# MaxMotornRF52840.net
KiCad netlist of a schematic drawn in EAGLE
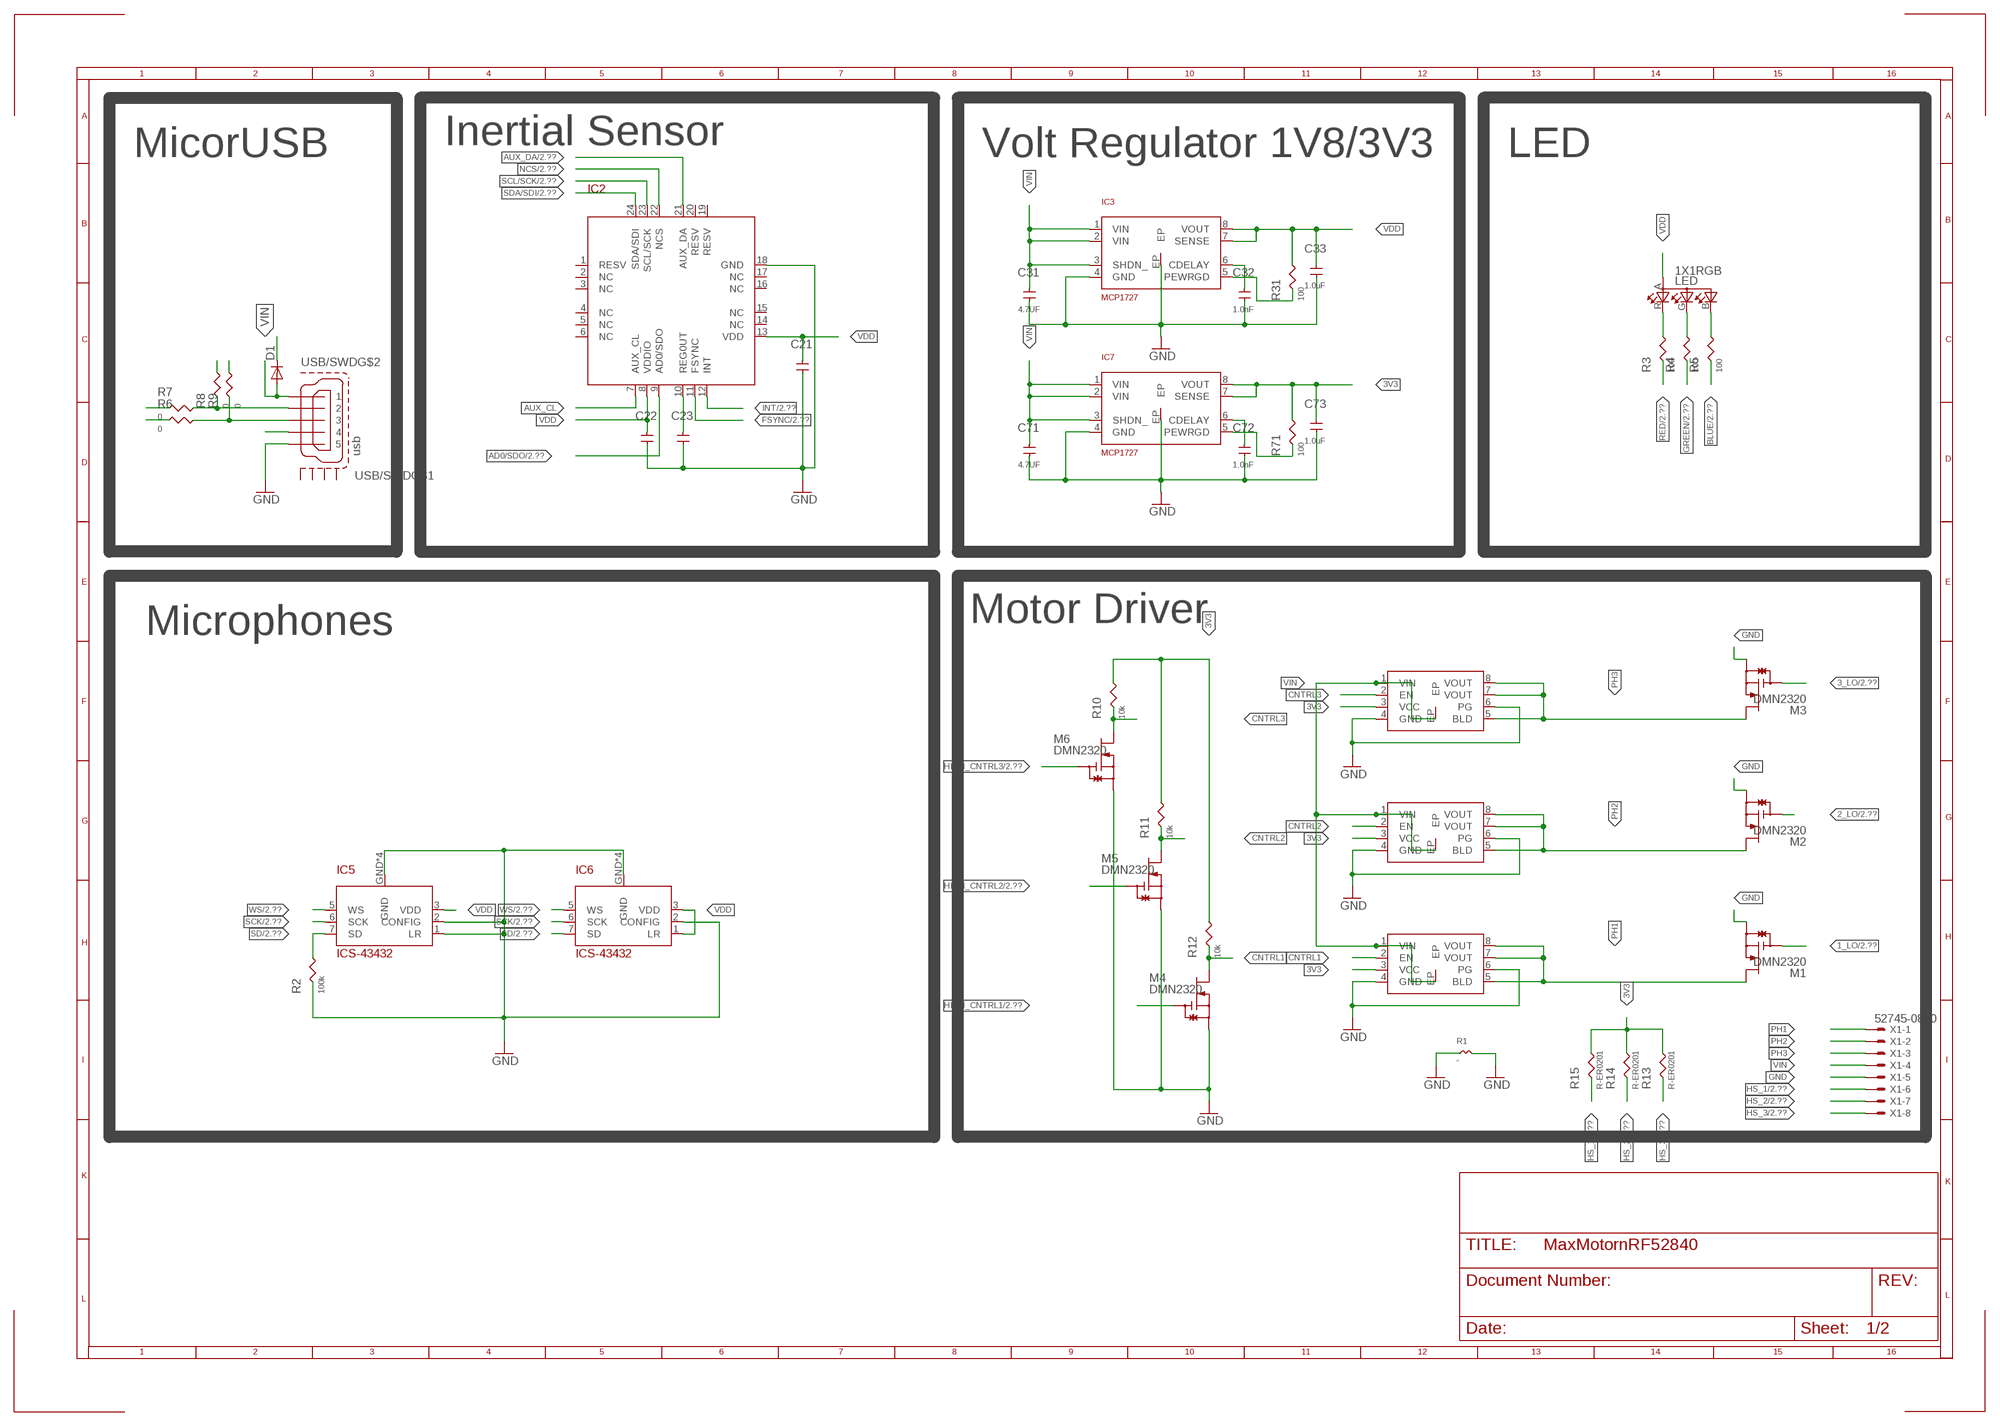
[diagram p0: schematic, sheet 1]
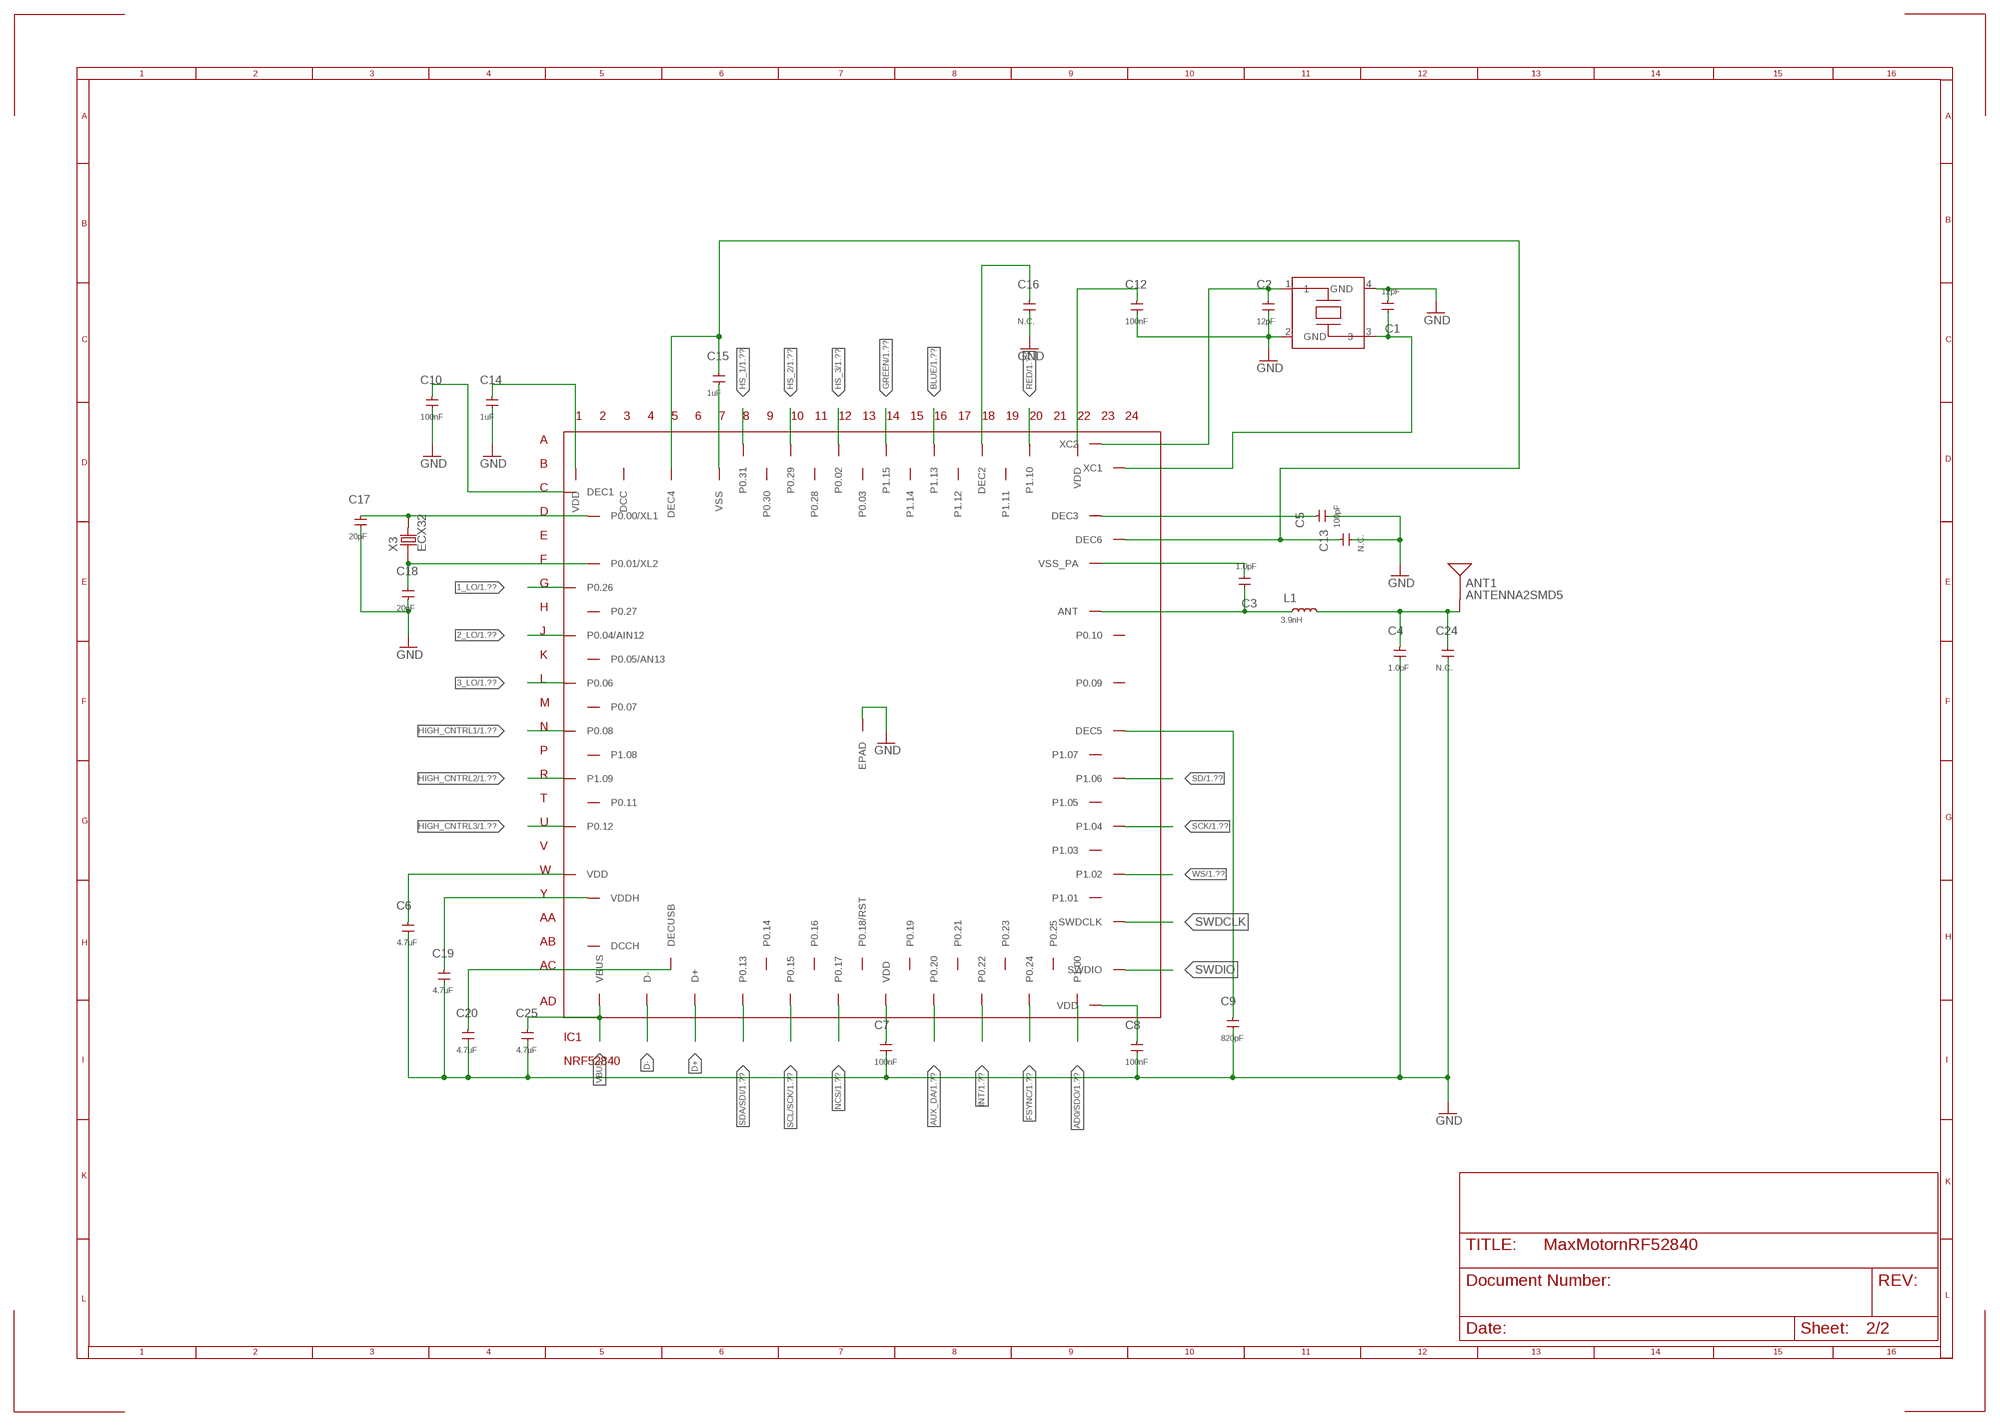
[diagram p1: schematic, sheet 2]

(export (version "E")
  (design (tool "Eeschema 10.0.6"))
  (components
    (comp (ref "ANT1")
      (value "ANTENNA2SMD5")
      (footprint "eagle-import:ANTENNA-CHIP5")
      (libsource (lib "eagle-import") (part "ANTENNA2SMD5"))
    )
    (comp (ref "C1")
      (value "12pF")
      (footprint "eagle-import:C0201")
      (libsource (lib "eagle-import") (part "C-ER201"))
    )
    (comp (ref "C2")
      (value "12pF")
      (footprint "eagle-import:C0201")
      (libsource (lib "eagle-import") (part "C-ER201"))
    )
    (comp (ref "C3")
      (value "1.0pF")
      (footprint "eagle-import:C0201")
      (libsource (lib "eagle-import") (part "C-ER201"))
    )
    (comp (ref "C4")
      (value "1.0pF")
      (footprint "eagle-import:C0201")
      (libsource (lib "eagle-import") (part "C-ER201"))
    )
    (comp (ref "C5")
      (value "100pF")
      (footprint "eagle-import:C0201")
      (libsource (lib "eagle-import") (part "C-ER201"))
    )
    (comp (ref "C6")
      (value "4.7uF")
      (footprint "eagle-import:C0402")
      (libsource (lib "eagle-import") (part "C-ERC0402"))
    )
    (comp (ref "C7")
      (value "100nF")
      (footprint "eagle-import:C0201")
      (libsource (lib "eagle-import") (part "C-ER201"))
    )
    (comp (ref "C8")
      (value "100nF")
      (footprint "eagle-import:C0201")
      (libsource (lib "eagle-import") (part "C-ER201"))
    )
    (comp (ref "C9")
      (value "820pF")
      (footprint "eagle-import:C0201")
      (libsource (lib "eagle-import") (part "C-ER201"))
    )
    (comp (ref "C10")
      (value "100nF")
      (footprint "eagle-import:C0201")
      (libsource (lib "eagle-import") (part "C-ER201"))
    )
    (comp (ref "C12")
      (value "100nF")
      (footprint "eagle-import:C0201")
      (libsource (lib "eagle-import") (part "C-ER201"))
    )
    (comp (ref "C13")
      (value "N.C.")
      (footprint "eagle-import:C0201")
      (libsource (lib "eagle-import") (part "C-ER201"))
    )
    (comp (ref "C14")
      (value "1uF")
      (footprint "eagle-import:C0201")
      (libsource (lib "eagle-import") (part "C-ER201"))
    )
    (comp (ref "C15")
      (value "1uF")
      (footprint "eagle-import:C0201")
      (libsource (lib "eagle-import") (part "C-ER201"))
    )
    (comp (ref "C16")
      (value "N.C.")
      (footprint "eagle-import:C0201")
      (libsource (lib "eagle-import") (part "C-ER201"))
    )
    (comp (ref "C17")
      (value "20pF")
      (footprint "eagle-import:C0201")
      (libsource (lib "eagle-import") (part "C-ER201"))
    )
    (comp (ref "C18")
      (value "20pF")
      (footprint "eagle-import:C0201")
      (libsource (lib "eagle-import") (part "C-ER201"))
    )
    (comp (ref "C19")
      (value "4.7uF")
      (footprint "eagle-import:C0402")
      (libsource (lib "eagle-import") (part "C-ERC0402"))
    )
    (comp (ref "C20")
      (value "4.7uF")
      (footprint "eagle-import:C0402")
      (libsource (lib "eagle-import") (part "C-ERC0402"))
    )
    (comp (ref "C24")
      (value "N.C.")
      (footprint "eagle-import:C0201")
      (libsource (lib "eagle-import") (part "C-ER201"))
    )
    (comp (ref "C25")
      (value "4.7uF")
      (footprint "eagle-import:C0402")
      (libsource (lib "eagle-import") (part "C-ERC0402"))
    )
    (comp (ref "IC1")
      (value "NRF52840")
      (footprint "eagle-import:AQFN73")
      (libsource (lib "eagle-import") (part "NRF52840"))
    )
    (comp (ref "L1")
      (value "3.9nH")
      (footprint "eagle-import:C0201@1")
      (libsource (lib "eagle-import") (part "L-ER0201"))
    )
    (comp (ref "X2")
      (value "ABM12")
      (footprint "eagle-import:ABM12")
      (libsource (lib "eagle-import") (part "ABM12"))
    )
    (comp (ref "X3")
      (value "ECX32")
      (footprint "eagle-import:ECX39")
      (libsource (lib "eagle-import") (part "ECX32"))
    )
    (comp (ref "C21")
      (value "C-ER201")
      (footprint "eagle-import:C0201")
      (libsource (lib "eagle-import") (part "C-ER201"))
    )
    (comp (ref "C22")
      (value "C-ER201")
      (footprint "eagle-import:C0201")
      (libsource (lib "eagle-import") (part "C-ER201"))
    )
    (comp (ref "C23")
      (value "C-ER201")
      (footprint "eagle-import:C0201")
      (libsource (lib "eagle-import") (part "C-ER201"))
    )
    (comp (ref "C31")
      (value "4.7UF")
      (footprint "eagle-import:C0402")
      (libsource (lib "eagle-import") (part "C-ERC0402"))
    )
    (comp (ref "C32")
      (value "1.0nF")
      (footprint "eagle-import:C0201")
      (libsource (lib "eagle-import") (part "C-ER201"))
    )
    (comp (ref "C33")
      (value "1.0uF")
      (footprint "eagle-import:C0201")
      (libsource (lib "eagle-import") (part "C-ER201"))
    )
    (comp (ref "C71")
      (value "4.7UF")
      (footprint "eagle-import:C0402")
      (libsource (lib "eagle-import") (part "C-ERC0402"))
    )
    (comp (ref "C72")
      (value "1.0nF")
      (footprint "eagle-import:C0201")
      (libsource (lib "eagle-import") (part "C-ER201"))
    )
    (comp (ref "C73")
      (value "1.0uF")
      (footprint "eagle-import:C0201")
      (libsource (lib "eagle-import") (part "C-ER201"))
    )
    (comp (ref "D1")
      (value "DIODE-SOD123")
      (footprint "eagle-import:SOD123")
      (libsource (lib "eagle-import") (part "DIODE-SOD123"))
    )
    (comp (ref "IC2")
      (value "ICM20948")
      (footprint "eagle-import:3X3_24_QFN_CORRECTED")
      (libsource (lib "eagle-import") (part "ICM20948"))
    )
    (comp (ref "IC3")
      (value "MCP1727")
      (footprint "eagle-import:DFN8-3X3")
      (libsource (lib "eagle-import") (part "MCP1727"))
    )
    (comp (ref "IC5")
      (value "ICS-43432")
      (footprint "eagle-import:ICS-43432")
      (libsource (lib "eagle-import") (part "ICS-43432"))
    )
    (comp (ref "IC6")
      (value "ICS-43432")
      (footprint "eagle-import:ICS-43432")
      (libsource (lib "eagle-import") (part "ICS-43432"))
    )
    (comp (ref "IC7")
      (value "MCP1727")
      (footprint "eagle-import:DFN8-3X3")
      (libsource (lib "eagle-import") (part "MCP1727"))
    )
    (comp (ref "LED")
      (value "1X1RGB")
      (footprint "eagle-import:1X1")
      (libsource (lib "eagle-import") (part "1X1RGB"))
    )
    (comp (ref "M1")
      (value "DMN2320")
      (footprint "eagle-import:AP02002")
      (libsource (lib "eagle-import") (part "DMN2320"))
    )
    (comp (ref "M2")
      (value "DMN2320")
      (footprint "eagle-import:AP02002")
      (libsource (lib "eagle-import") (part "DMN2320"))
    )
    (comp (ref "M3")
      (value "DMN2320")
      (footprint "eagle-import:AP02002")
      (libsource (lib "eagle-import") (part "DMN2320"))
    )
    (comp (ref "M4")
      (value "DMN2320")
      (footprint "eagle-import:AP02002")
      (libsource (lib "eagle-import") (part "DMN2320"))
    )
    (comp (ref "M5")
      (value "DMN2320")
      (footprint "eagle-import:AP02002")
      (libsource (lib "eagle-import") (part "DMN2320"))
    )
    (comp (ref "M6")
      (value "DMN2320")
      (footprint "eagle-import:AP02002")
      (libsource (lib "eagle-import") (part "DMN2320"))
    )
    (comp (ref "M7")
      (value "NCP45524/25")
      (footprint "eagle-import:DFN8")
      (libsource (lib "eagle-import") (part "NCP45524/25"))
    )
    (comp (ref "M8")
      (value "NCP45524/25")
      (footprint "eagle-import:DFN8")
      (libsource (lib "eagle-import") (part "NCP45524/25"))
    )
    (comp (ref "M9")
      (value "NCP45524/25")
      (footprint "eagle-import:DFN8")
      (libsource (lib "eagle-import") (part "NCP45524/25"))
    )
    (comp (ref "R1")
      (value "0")
      (footprint "eagle-import:R0805")
      (libsource (lib "eagle-import") (part "R-ER-TINY"))
    )
    (comp (ref "R2")
      (value "100k")
      (footprint "eagle-import:R0201")
      (libsource (lib "eagle-import") (part "R-ER0201"))
    )
    (comp (ref "R3")
      (value "100")
      (footprint "eagle-import:R0201")
      (libsource (lib "eagle-import") (part "R-ER0201"))
    )
    (comp (ref "R4")
      (value "100")
      (footprint "eagle-import:R0201")
      (libsource (lib "eagle-import") (part "R-ER0201"))
    )
    (comp (ref "R5")
      (value "100")
      (footprint "eagle-import:R0201")
      (libsource (lib "eagle-import") (part "R-ER0201"))
    )
    (comp (ref "R6")
      (value "0")
      (footprint "eagle-import:R0201")
      (libsource (lib "eagle-import") (part "R-ER0201"))
    )
    (comp (ref "R7")
      (value "0")
      (footprint "eagle-import:R0201")
      (libsource (lib "eagle-import") (part "R-ER0201"))
    )
    (comp (ref "R8")
      (value "0")
      (footprint "eagle-import:R0201")
      (libsource (lib "eagle-import") (part "R-ER0201"))
    )
    (comp (ref "R9")
      (value "0")
      (footprint "eagle-import:R0201")
      (libsource (lib "eagle-import") (part "R-ER0201"))
    )
    (comp (ref "R10")
      (value "10k")
      (footprint "eagle-import:R0201")
      (libsource (lib "eagle-import") (part "R-ER0201"))
    )
    (comp (ref "R11")
      (value "10k")
      (footprint "eagle-import:R0201")
      (libsource (lib "eagle-import") (part "R-ER0201"))
    )
    (comp (ref "R12")
      (value "10k")
      (footprint "eagle-import:R0201")
      (libsource (lib "eagle-import") (part "R-ER0201"))
    )
    (comp (ref "R13")
      (value "R-ER0201")
      (footprint "eagle-import:R0201")
      (libsource (lib "eagle-import") (part "R-ER0201"))
    )
    (comp (ref "R14")
      (value "R-ER0201")
      (footprint "eagle-import:R0201")
      (libsource (lib "eagle-import") (part "R-ER0201"))
    )
    (comp (ref "R15")
      (value "R-ER0201")
      (footprint "eagle-import:R0201")
      (libsource (lib "eagle-import") (part "R-ER0201"))
    )
    (comp (ref "R31")
      (value "100")
      (footprint "eagle-import:R0201")
      (libsource (lib "eagle-import") (part "R-ER0201"))
    )
    (comp (ref "R71")
      (value "100")
      (footprint "eagle-import:R0201")
      (libsource (lib "eagle-import") (part "R-ER0201"))
    )
    (comp (ref "USB/SWD")
      (value "usb")
      (footprint "eagle-import:ZX62R-B-5P")
      (libsource (lib "eagle-import") (part "MICRO-USB-SHIELD-ZX62R-B-5P"))
    )
    (comp (ref "X1")
      (value "52745-0890")
      (footprint "eagle-import:52745-0890")
      (libsource (lib "eagle-import") (part "52745-0890"))
    )
  )
  (nets
    (net (code "1") (name "1_LO") (class "Default")
      (node (ref "IC1") (pin "G1") (pinfunction "P0.26_G1") (pintype "bidirectional"))
      (node (ref "M1") (pin "G") (pinfunction "G_G") (pintype "passive"))
    )
    (net (code "2") (name "2_LO") (class "Default")
      (node (ref "IC1") (pin "J1") (pinfunction "P0.04/AIN12_J1") (pintype "bidirectional"))
      (node (ref "M2") (pin "G") (pinfunction "G_G") (pintype "passive"))
    )
    (net (code "3") (name "3V3") (class "Default")
      (node (ref "C73") (pin "2") (pinfunction "P$2_2") (pintype "bidirectional"))
      (node (ref "IC7") (pin "7") (pinfunction "SENSE_7") (pintype "bidirectional"))
      (node (ref "IC7") (pin "8") (pinfunction "VOUT_8") (pintype "bidirectional"))
      (node (ref "M7") (pin "3") (pinfunction "VCC_3") (pintype "bidirectional"))
      (node (ref "M8") (pin "3") (pinfunction "VCC_3") (pintype "bidirectional"))
      (node (ref "M9") (pin "3") (pinfunction "VCC_3") (pintype "bidirectional"))
      (node (ref "R10") (pin "2") (pinfunction "P$2_2") (pintype "bidirectional"))
      (node (ref "R11") (pin "2") (pinfunction "P$2_2") (pintype "bidirectional"))
      (node (ref "R12") (pin "2") (pinfunction "P$2_2") (pintype "bidirectional"))
      (node (ref "R13") (pin "2") (pinfunction "P$2_2") (pintype "bidirectional"))
      (node (ref "R14") (pin "2") (pinfunction "P$2_2") (pintype "bidirectional"))
      (node (ref "R15") (pin "2") (pinfunction "P$2_2") (pintype "bidirectional"))
      (node (ref "R71") (pin "2") (pinfunction "P$2_2") (pintype "bidirectional"))
    )
    (net (code "4") (name "3_LO") (class "Default")
      (node (ref "IC1") (pin "L1") (pinfunction "P0.06_L1") (pintype "bidirectional"))
      (node (ref "M3") (pin "G") (pinfunction "G_G") (pintype "passive"))
    )
    (net (code "5") (name "AD0{slash}SDO") (class "Default")
      (node (ref "IC1") (pin "AD22") (pinfunction "P1.00_AD22") (pintype "bidirectional"))
      (node (ref "IC2") (pin "9") (pinfunction "AD0/SDO_9") (pintype "bidirectional"))
    )
    (net (code "6") (name "AUX_CL") (class "Default")
      (node (ref "IC2") (pin "7") (pinfunction "AUX_CL_7") (pintype "bidirectional"))
    )
    (net (code "7") (name "AUX_DA") (class "Default")
      (node (ref "IC1") (pin "AD16") (pinfunction "P0.20_AD16") (pintype "bidirectional"))
      (node (ref "IC2") (pin "21") (pinfunction "AUX_DA_21") (pintype "bidirectional"))
    )
    (net (code "8") (name "BLUE") (class "Default")
      (node (ref "IC1") (pin "A16") (pinfunction "P1.13_A16") (pintype "bidirectional"))
      (node (ref "R5") (pin "1") (pinfunction "P$1_1") (pintype "bidirectional"))
    )
    (net (code "9") (name "CNTRL1") (class "Default")
      (node (ref "M4") (pin "D") (pinfunction "D_D") (pintype "passive"))
      (node (ref "M7") (pin "2") (pinfunction "EN_2") (pintype "bidirectional"))
      (node (ref "R12") (pin "1") (pinfunction "P$1_1") (pintype "bidirectional"))
    )
    (net (code "10") (name "CNTRL2") (class "Default")
      (node (ref "M5") (pin "D") (pinfunction "D_D") (pintype "passive"))
      (node (ref "M8") (pin "2") (pinfunction "EN_2") (pintype "bidirectional"))
      (node (ref "R11") (pin "1") (pinfunction "P$1_1") (pintype "bidirectional"))
    )
    (net (code "11") (name "CNTRL3") (class "Default")
      (node (ref "M6") (pin "D") (pinfunction "D_D") (pintype "passive"))
      (node (ref "M9") (pin "2") (pinfunction "EN_2") (pintype "bidirectional"))
      (node (ref "R10") (pin "1") (pinfunction "P$1_1") (pintype "bidirectional"))
    )
    (net (code "12") (name "D+") (class "Default")
      (node (ref "IC1") (pin "AD6") (pinfunction "D+_AD6") (pintype "bidirectional"))
      (node (ref "R6") (pin "1") (pinfunction "P$1_1") (pintype "bidirectional"))
    )
    (net (code "13") (name "D-") (class "Default")
      (node (ref "IC1") (pin "AD4") (pinfunction "D-_AD4") (pintype "bidirectional"))
      (node (ref "R7") (pin "1") (pinfunction "P$1_1") (pintype "bidirectional"))
    )
    (net (code "14") (name "FSYNC") (class "Default")
      (node (ref "IC1") (pin "AD20") (pinfunction "P0.24_AD20") (pintype "bidirectional"))
      (node (ref "IC2") (pin "11") (pinfunction "FSYNC_11") (pintype "bidirectional"))
    )
    (net (code "15") (name "GND") (class "Default")
      (node (ref "C1") (pin "1") (pinfunction "P$1_1") (pintype "bidirectional"))
      (node (ref "C10") (pin "1") (pinfunction "P$1_1") (pintype "bidirectional"))
      (node (ref "C12") (pin "1") (pinfunction "P$1_1") (pintype "bidirectional"))
      (node (ref "C13") (pin "1") (pinfunction "P$1_1") (pintype "bidirectional"))
      (node (ref "C14") (pin "1") (pinfunction "P$1_1") (pintype "bidirectional"))
      (node (ref "C15") (pin "1") (pinfunction "P$1_1") (pintype "bidirectional"))
      (node (ref "C16") (pin "1") (pinfunction "P$1_1") (pintype "bidirectional"))
      (node (ref "C17") (pin "1") (pinfunction "P$1_1") (pintype "bidirectional"))
      (node (ref "C18") (pin "1") (pinfunction "P$1_1") (pintype "bidirectional"))
      (node (ref "C19") (pin "1") (pinfunction "P$1_1") (pintype "bidirectional"))
      (node (ref "C2") (pin "1") (pinfunction "P$1_1") (pintype "bidirectional"))
      (node (ref "C20") (pin "1") (pinfunction "P$1_1") (pintype "bidirectional"))
      (node (ref "C21") (pin "1") (pinfunction "P$1_1") (pintype "bidirectional"))
      (node (ref "C22") (pin "1") (pinfunction "P$1_1") (pintype "bidirectional"))
      (node (ref "C23") (pin "1") (pinfunction "P$1_1") (pintype "bidirectional"))
      (node (ref "C24") (pin "1") (pinfunction "P$1_1") (pintype "bidirectional"))
      (node (ref "C25") (pin "1") (pinfunction "P$1_1") (pintype "bidirectional"))
      (node (ref "C3") (pin "1") (pinfunction "P$1_1") (pintype "bidirectional"))
      (node (ref "C31") (pin "1") (pinfunction "P$1_1") (pintype "bidirectional"))
      (node (ref "C32") (pin "1") (pinfunction "P$1_1") (pintype "bidirectional"))
      (node (ref "C33") (pin "1") (pinfunction "P$1_1") (pintype "bidirectional"))
      (node (ref "C4") (pin "1") (pinfunction "P$1_1") (pintype "bidirectional"))
      (node (ref "C5") (pin "1") (pinfunction "P$1_1") (pintype "bidirectional"))
      (node (ref "C6") (pin "1") (pinfunction "P$1_1") (pintype "bidirectional"))
      (node (ref "C7") (pin "1") (pinfunction "P$1_1") (pintype "bidirectional"))
      (node (ref "C71") (pin "1") (pinfunction "P$1_1") (pintype "bidirectional"))
      (node (ref "C72") (pin "1") (pinfunction "P$1_1") (pintype "bidirectional"))
      (node (ref "C73") (pin "1") (pinfunction "P$1_1") (pintype "bidirectional"))
      (node (ref "C8") (pin "1") (pinfunction "P$1_1") (pintype "bidirectional"))
      (node (ref "C9") (pin "1") (pinfunction "P$1_1") (pintype "bidirectional"))
      (node (ref "IC1") (pin "B7") (pinfunction "VSS_B7") (pintype "bidirectional"))
      (node (ref "IC1") (pin "EPAD") (pinfunction "EPAD_EPAD") (pintype "bidirectional"))
      (node (ref "IC1") (pin "F23") (pinfunction "VSS_PA_F23") (pintype "bidirectional"))
      (node (ref "IC2") (pin "18") (pinfunction "GND_18") (pintype "bidirectional"))
      (node (ref "IC3") (pin "4") (pinfunction "GND_4") (pintype "bidirectional"))
      (node (ref "IC3") (pin "EP") (pinfunction "EP_EP") (pintype "bidirectional"))
      (node (ref "IC5") (pin "1") (pinfunction "LR_1") (pintype "bidirectional"))
      (node (ref "IC5") (pin "2") (pinfunction "CONFIG_2") (pintype "bidirectional"))
      (node (ref "IC5") (pin "GND") (pinfunction "GND_GND") (pintype "bidirectional"))
      (node (ref "IC5") (pin "GND@") (pinfunction "GND_GND@") (pintype "bidirectional"))
      (node (ref "IC5") (pin "GND@1") (pinfunction "GND_GND@1") (pintype "bidirectional"))
      (node (ref "IC5") (pin "GND@2") (pinfunction "GND_GND@2") (pintype "bidirectional"))
      (node (ref "IC6") (pin "2") (pinfunction "CONFIG_2") (pintype "bidirectional"))
      (node (ref "IC6") (pin "GND") (pinfunction "GND_GND") (pintype "bidirectional"))
      (node (ref "IC6") (pin "GND@") (pinfunction "GND_GND@") (pintype "bidirectional"))
      (node (ref "IC6") (pin "GND@1") (pinfunction "GND_GND@1") (pintype "bidirectional"))
      (node (ref "IC6") (pin "GND@2") (pinfunction "GND_GND@2") (pintype "bidirectional"))
      (node (ref "IC7") (pin "4") (pinfunction "GND_4") (pintype "bidirectional"))
      (node (ref "IC7") (pin "EP") (pinfunction "EP_EP") (pintype "bidirectional"))
      (node (ref "M1") (pin "S") (pinfunction "S_S") (pintype "passive"))
      (node (ref "M2") (pin "S") (pinfunction "S_S") (pintype "passive"))
      (node (ref "M3") (pin "S") (pinfunction "S_S") (pintype "passive"))
      (node (ref "M4") (pin "S") (pinfunction "S_S") (pintype "passive"))
      (node (ref "M5") (pin "S") (pinfunction "S_S") (pintype "passive"))
      (node (ref "M6") (pin "S") (pinfunction "S_S") (pintype "passive"))
      (node (ref "M7") (pin "4") (pinfunction "GND_4") (pintype "bidirectional"))
      (node (ref "M7") (pin "6") (pinfunction "PG_6") (pintype "bidirectional"))
      (node (ref "M8") (pin "4") (pinfunction "GND_4") (pintype "bidirectional"))
      (node (ref "M8") (pin "6") (pinfunction "PG_6") (pintype "bidirectional"))
      (node (ref "M9") (pin "4") (pinfunction "GND_4") (pintype "bidirectional"))
      (node (ref "M9") (pin "6") (pinfunction "PG_6") (pintype "bidirectional"))
      (node (ref "R1") (pin "1") (pinfunction "P$1_1") (pintype "bidirectional"))
      (node (ref "R1") (pin "2") (pinfunction "P$2_2") (pintype "bidirectional"))
      (node (ref "R2") (pin "1") (pinfunction "P$1_1") (pintype "bidirectional"))
      (node (ref "USB/SWD") (pin "1") (pinfunction "5_1") (pintype "input"))
      (node (ref "X1") (pin "5") (pinfunction "S_5") (pintype "passive"))
      (node (ref "X2") (pin "2") (pinfunction "GND_2") (pintype "bidirectional"))
      (node (ref "X2") (pin "4") (pinfunction "GND_4") (pintype "bidirectional"))
    )
    (net (code "16") (name "GREEN") (class "Default")
      (node (ref "IC1") (pin "A14") (pinfunction "P1.15_A14") (pintype "bidirectional"))
      (node (ref "R4") (pin "1") (pinfunction "P$1_1") (pintype "bidirectional"))
    )
    (net (code "17") (name "HIGH_CNTRL1") (class "Default")
      (node (ref "IC1") (pin "N1") (pinfunction "P0.08_N1") (pintype "bidirectional"))
      (node (ref "M4") (pin "G") (pinfunction "G_G") (pintype "passive"))
    )
    (net (code "18") (name "HIGH_CNTRL2") (class "Default")
      (node (ref "IC1") (pin "R1") (pinfunction "P1.09_R1") (pintype "bidirectional"))
      (node (ref "M5") (pin "G") (pinfunction "G_G") (pintype "passive"))
    )
    (net (code "19") (name "HIGH_CNTRL3") (class "Default")
      (node (ref "IC1") (pin "U1") (pinfunction "P0.12_U1") (pintype "bidirectional"))
      (node (ref "M6") (pin "G") (pinfunction "G_G") (pintype "passive"))
    )
    (net (code "20") (name "HS_1") (class "Default")
      (node (ref "IC1") (pin "A8") (pinfunction "P0.31_A8") (pintype "bidirectional"))
      (node (ref "R15") (pin "1") (pinfunction "P$1_1") (pintype "bidirectional"))
      (node (ref "X1") (pin "6") (pinfunction "S_6") (pintype "passive"))
    )
    (net (code "21") (name "HS_2") (class "Default")
      (node (ref "IC1") (pin "A10") (pinfunction "P0.29_A10") (pintype "bidirectional"))
      (node (ref "R14") (pin "1") (pinfunction "P$1_1") (pintype "bidirectional"))
      (node (ref "X1") (pin "7") (pinfunction "S_7") (pintype "passive"))
    )
    (net (code "22") (name "HS_3") (class "Default")
      (node (ref "IC1") (pin "A12") (pinfunction "P0.02_A12") (pintype "bidirectional"))
      (node (ref "R13") (pin "1") (pinfunction "P$1_1") (pintype "bidirectional"))
      (node (ref "X1") (pin "8") (pinfunction "S_8") (pintype "passive"))
    )
    (net (code "23") (name "INT") (class "Default")
      (node (ref "IC1") (pin "AD18") (pinfunction "P0.22_AD18") (pintype "bidirectional"))
      (node (ref "IC2") (pin "12") (pinfunction "INT_12") (pintype "bidirectional"))
    )
    (net (code "24") (name "NCS") (class "Default")
      (node (ref "IC1") (pin "AD12") (pinfunction "P0.17_AD12") (pintype "bidirectional"))
      (node (ref "IC2") (pin "22") (pinfunction "NCS_22") (pintype "bidirectional"))
    )
    (net (code "25") (name "Net-(ANT1-SIGNAL)") (class "Default")
      (node (ref "ANT1") (pin "FEED") (pinfunction "SIGNAL_FEED") (pintype "bidirectional"))
      (node (ref "C24") (pin "2") (pinfunction "P$2_2") (pintype "bidirectional"))
      (node (ref "C4") (pin "2") (pinfunction "P$2_2") (pintype "bidirectional"))
      (node (ref "L1") (pin "2") (pinfunction "P$2_2") (pintype "bidirectional"))
    )
    (net (code "26") (name "Net-(C1-P$2)") (class "Default")
      (node (ref "C1") (pin "2") (pinfunction "P$2_2") (pintype "bidirectional"))
      (node (ref "IC1") (pin "B24") (pinfunction "XC1_B24") (pintype "bidirectional"))
      (node (ref "X2") (pin "3") (pinfunction "3_3") (pintype "bidirectional"))
    )
    (net (code "27") (name "Net-(C2-P$2)") (class "Default")
      (node (ref "C2") (pin "2") (pinfunction "P$2_2") (pintype "bidirectional"))
      (node (ref "IC1") (pin "A23") (pinfunction "XC2_A23") (pintype "bidirectional"))
      (node (ref "X2") (pin "1") (pinfunction "1_1") (pintype "bidirectional"))
    )
    (net (code "28") (name "Net-(C3-P$2)") (class "Default")
      (node (ref "C3") (pin "2") (pinfunction "P$2_2") (pintype "bidirectional"))
      (node (ref "IC1") (pin "H23") (pinfunction "ANT_H23") (pintype "bidirectional"))
      (node (ref "L1") (pin "1") (pinfunction "P$1_1") (pintype "bidirectional"))
    )
    (net (code "29") (name "Net-(C5-P$2)") (class "Default")
      (node (ref "C5") (pin "2") (pinfunction "P$2_2") (pintype "bidirectional"))
      (node (ref "IC1") (pin "D23") (pinfunction "DEC3_D23") (pintype "bidirectional"))
    )
    (net (code "30") (name "Net-(C9-P$2)") (class "Default")
      (node (ref "C9") (pin "2") (pinfunction "P$2_2") (pintype "bidirectional"))
      (node (ref "IC1") (pin "N24") (pinfunction "DEC5_N24") (pintype "bidirectional"))
    )
    (net (code "31") (name "Net-(C13-P$2)") (class "Default")
      (node (ref "C13") (pin "2") (pinfunction "P$2_2") (pintype "bidirectional"))
      (node (ref "C15") (pin "2") (pinfunction "P$2_2") (pintype "bidirectional"))
      (node (ref "IC1") (pin "B5") (pinfunction "DEC4_B5") (pintype "bidirectional"))
      (node (ref "IC1") (pin "E24") (pinfunction "DEC6_E24") (pintype "bidirectional"))
    )
    (net (code "32") (name "Net-(C14-P$2)") (class "Default")
      (node (ref "C14") (pin "2") (pinfunction "P$2_2") (pintype "bidirectional"))
      (node (ref "IC1") (pin "B1") (pinfunction "VDD_B1") (pintype "bidirectional"))
    )
    (net (code "33") (name "Net-(C16-P$2)") (class "Default")
      (node (ref "C16") (pin "2") (pinfunction "P$2_2") (pintype "bidirectional"))
      (node (ref "IC1") (pin "A18") (pinfunction "DEC2_A18") (pintype "bidirectional"))
    )
    (net (code "34") (name "Net-(C17-P$2)") (class "Default")
      (node (ref "C17") (pin "2") (pinfunction "P$2_2") (pintype "bidirectional"))
      (node (ref "IC1") (pin "D2") (pinfunction "P0.00/XL1_D2") (pintype "bidirectional"))
      (node (ref "X3") (pin "P$2") (pinfunction "2_P$2") (pintype "passive"))
    )
    (net (code "35") (name "Net-(C18-P$2)") (class "Default")
      (node (ref "C18") (pin "2") (pinfunction "P$2_2") (pintype "bidirectional"))
      (node (ref "IC1") (pin "F2") (pinfunction "P0.01/XL2_F2") (pintype "bidirectional"))
      (node (ref "X3") (pin "P$1") (pinfunction "1_P$1") (pintype "passive"))
    )
    (net (code "36") (name "Net-(C20-P$2)") (class "Default")
      (node (ref "C20") (pin "2") (pinfunction "P$2_2") (pintype "bidirectional"))
      (node (ref "IC1") (pin "AC5") (pinfunction "DECUSB_AC5") (pintype "bidirectional"))
    )
    (net (code "37") (name "Net-(C23-P$2)") (class "Default")
      (node (ref "C23") (pin "2") (pinfunction "P$2_2") (pintype "bidirectional"))
      (node (ref "IC2") (pin "10") (pinfunction "REG0UT_10") (pintype "bidirectional"))
    )
    (net (code "38") (name "Net-(C32-P$2)") (class "Default")
      (node (ref "C32") (pin "2") (pinfunction "P$2_2") (pintype "bidirectional"))
      (node (ref "IC3") (pin "6") (pinfunction "CDELAY_6") (pintype "bidirectional"))
    )
    (net (code "39") (name "Net-(C72-P$2)") (class "Default")
      (node (ref "C72") (pin "2") (pinfunction "P$2_2") (pintype "bidirectional"))
      (node (ref "IC7") (pin "6") (pinfunction "CDELAY_6") (pintype "bidirectional"))
    )
    (net (code "40") (name "Net-(IC3-PEWRGD)") (class "Default")
      (node (ref "IC3") (pin "5") (pinfunction "PEWRGD_5") (pintype "bidirectional"))
      (node (ref "R31") (pin "1") (pinfunction "P$1_1") (pintype "bidirectional"))
    )
    (net (code "41") (name "Net-(IC7-PEWRGD)") (class "Default")
      (node (ref "IC7") (pin "5") (pinfunction "PEWRGD_5") (pintype "bidirectional"))
      (node (ref "R71") (pin "1") (pinfunction "P$1_1") (pintype "bidirectional"))
    )
    (net (code "42") (name "Net-(LED-CBLUE)") (class "Default")
      (node (ref "LED") (pin "G") (pinfunction "CBLUE_G") (pintype "passive"))
      (node (ref "R4") (pin "2") (pinfunction "P$2_2") (pintype "bidirectional"))
    )
    (net (code "43") (name "Net-(LED-CGREEN)") (class "Default")
      (node (ref "LED") (pin "B") (pinfunction "CGREEN_B") (pintype "passive"))
      (node (ref "R5") (pin "2") (pinfunction "P$2_2") (pintype "bidirectional"))
    )
    (net (code "44") (name "Net-(LED-CRED)") (class "Default")
      (node (ref "LED") (pin "R") (pinfunction "CRED_R") (pintype "passive"))
      (node (ref "R3") (pin "2") (pinfunction "P$2_2") (pintype "bidirectional"))
    )
    (net (code "45") (name "Net-(R6-P$2)") (class "Default")
      (node (ref "R6") (pin "2") (pinfunction "P$2_2") (pintype "bidirectional"))
      (node (ref "R9") (pin "1") (pinfunction "P$1_1") (pintype "bidirectional"))
      (node (ref "USB/SWD") (pin "3") (pinfunction "3_3") (pintype "input"))
    )
    (net (code "46") (name "Net-(R7-P$2)") (class "Default")
      (node (ref "R7") (pin "2") (pinfunction "P$2_2") (pintype "bidirectional"))
      (node (ref "R8") (pin "1") (pinfunction "P$1_1") (pintype "bidirectional"))
      (node (ref "USB/SWD") (pin "4") (pinfunction "2_4") (pintype "input"))
    )
    (net (code "47") (name "PH1") (class "Default")
      (node (ref "M1") (pin "D") (pinfunction "D_D") (pintype "passive"))
      (node (ref "M7") (pin "5") (pinfunction "BLD_5") (pintype "bidirectional"))
      (node (ref "M7") (pin "7") (pinfunction "VOUT_7") (pintype "bidirectional"))
      (node (ref "M7") (pin "8") (pinfunction "VOUT_8") (pintype "bidirectional"))
      (node (ref "X1") (pin "1") (pinfunction "S_1") (pintype "passive"))
    )
    (net (code "48") (name "PH2") (class "Default")
      (node (ref "M2") (pin "D") (pinfunction "D_D") (pintype "passive"))
      (node (ref "M8") (pin "5") (pinfunction "BLD_5") (pintype "bidirectional"))
      (node (ref "M8") (pin "7") (pinfunction "VOUT_7") (pintype "bidirectional"))
      (node (ref "M8") (pin "8") (pinfunction "VOUT_8") (pintype "bidirectional"))
      (node (ref "X1") (pin "2") (pinfunction "S_2") (pintype "passive"))
    )
    (net (code "49") (name "PH3") (class "Default")
      (node (ref "M3") (pin "D") (pinfunction "D_D") (pintype "passive"))
      (node (ref "M9") (pin "5") (pinfunction "BLD_5") (pintype "bidirectional"))
      (node (ref "M9") (pin "7") (pinfunction "VOUT_7") (pintype "bidirectional"))
      (node (ref "M9") (pin "8") (pinfunction "VOUT_8") (pintype "bidirectional"))
      (node (ref "X1") (pin "3") (pinfunction "S_3") (pintype "passive"))
    )
    (net (code "50") (name "RED") (class "Default")
      (node (ref "IC1") (pin "A20") (pinfunction "P1.10_A20") (pintype "bidirectional"))
      (node (ref "R3") (pin "1") (pinfunction "P$1_1") (pintype "bidirectional"))
    )
    (net (code "51") (name "SCK") (class "Default")
      (node (ref "IC1") (pin "U24") (pinfunction "P1.04_U24") (pintype "bidirectional"))
      (node (ref "IC5") (pin "6") (pinfunction "SCK_6") (pintype "bidirectional"))
      (node (ref "IC6") (pin "6") (pinfunction "SCK_6") (pintype "bidirectional"))
    )
    (net (code "52") (name "SCL{slash}SCK") (class "Default")
      (node (ref "IC1") (pin "AD10") (pinfunction "P0.15_AD10") (pintype "bidirectional"))
      (node (ref "IC2") (pin "23") (pinfunction "SCL/SCK_23") (pintype "bidirectional"))
    )
    (net (code "53") (name "SD") (class "Default")
      (node (ref "IC1") (pin "R24") (pinfunction "P1.06_R24") (pintype "bidirectional"))
      (node (ref "IC5") (pin "7") (pinfunction "SD_7") (pintype "bidirectional"))
      (node (ref "IC6") (pin "7") (pinfunction "SD_7") (pintype "bidirectional"))
      (node (ref "R2") (pin "2") (pinfunction "P$2_2") (pintype "bidirectional"))
    )
    (net (code "54") (name "SDA{slash}SDI") (class "Default")
      (node (ref "IC1") (pin "AD8") (pinfunction "P0.13_AD8") (pintype "bidirectional"))
      (node (ref "IC2") (pin "24") (pinfunction "SDA/SDI_24") (pintype "bidirectional"))
    )
    (net (code "55") (name "SWDCLK") (class "Default")
      (node (ref "IC1") (pin "AA24") (pinfunction "SWDCLK_AA24") (pintype "bidirectional"))
      (node (ref "R9") (pin "2") (pinfunction "P$2_2") (pintype "bidirectional"))
    )
    (net (code "56") (name "SWDIO") (class "Default")
      (node (ref "IC1") (pin "AC24") (pinfunction "SWDIO_AC24") (pintype "bidirectional"))
      (node (ref "R8") (pin "2") (pinfunction "P$2_2") (pintype "bidirectional"))
    )
    (net (code "57") (name "VBUS") (class "Default")
      (node (ref "C19") (pin "2") (pinfunction "P$2_2") (pintype "bidirectional"))
      (node (ref "C25") (pin "2") (pinfunction "P$2_2") (pintype "bidirectional"))
      (node (ref "D1") (pin "C") (pinfunction "C_C") (pintype "passive"))
      (node (ref "IC1") (pin "AD2") (pinfunction "VBUS_AD2") (pintype "bidirectional"))
      (node (ref "IC1") (pin "Y2") (pinfunction "VDDH_Y2") (pintype "bidirectional"))
    )
    (net (code "58") (name "VDD") (class "Default")
      (node (ref "C10") (pin "2") (pinfunction "P$2_2") (pintype "bidirectional"))
      (node (ref "C12") (pin "2") (pinfunction "P$2_2") (pintype "bidirectional"))
      (node (ref "C21") (pin "2") (pinfunction "P$2_2") (pintype "bidirectional"))
      (node (ref "C22") (pin "2") (pinfunction "P$2_2") (pintype "bidirectional"))
      (node (ref "C33") (pin "2") (pinfunction "P$2_2") (pintype "bidirectional"))
      (node (ref "C6") (pin "2") (pinfunction "P$2_2") (pintype "bidirectional"))
      (node (ref "C7") (pin "2") (pinfunction "P$2_2") (pintype "bidirectional"))
      (node (ref "C8") (pin "2") (pinfunction "P$2_2") (pintype "bidirectional"))
      (node (ref "IC1") (pin "A22") (pinfunction "VDD_A22") (pintype "bidirectional"))
      (node (ref "IC1") (pin "AD14") (pinfunction "VDD_AD14") (pintype "bidirectional"))
      (node (ref "IC1") (pin "AD23") (pinfunction "VDD_AD23") (pintype "bidirectional"))
      (node (ref "IC1") (pin "C1") (pinfunction "DEC1_C1") (pintype "bidirectional"))
      (node (ref "IC1") (pin "W1") (pinfunction "VDD_W1") (pintype "bidirectional"))
      (node (ref "IC2") (pin "13") (pinfunction "VDD_13") (pintype "bidirectional"))
      (node (ref "IC2") (pin "8") (pinfunction "VDDIO_8") (pintype "bidirectional"))
      (node (ref "IC3") (pin "7") (pinfunction "SENSE_7") (pintype "bidirectional"))
      (node (ref "IC3") (pin "8") (pinfunction "VOUT_8") (pintype "bidirectional"))
      (node (ref "IC5") (pin "3") (pinfunction "VDD_3") (pintype "bidirectional"))
      (node (ref "IC6") (pin "1") (pinfunction "LR_1") (pintype "bidirectional"))
      (node (ref "IC6") (pin "3") (pinfunction "VDD_3") (pintype "bidirectional"))
      (node (ref "LED") (pin "A") (pinfunction "A2_A") (pintype "passive"))
      (node (ref "R31") (pin "2") (pinfunction "P$2_2") (pintype "bidirectional"))
    )
    (net (code "59") (name "VIN") (class "Default")
      (node (ref "C31") (pin "2") (pinfunction "P$2_2") (pintype "bidirectional"))
      (node (ref "C71") (pin "2") (pinfunction "P$2_2") (pintype "bidirectional"))
      (node (ref "D1") (pin "A") (pinfunction "A_A") (pintype "passive"))
      (node (ref "IC3") (pin "1") (pinfunction "VIN_1") (pintype "bidirectional"))
      (node (ref "IC3") (pin "2") (pinfunction "VIN_2") (pintype "bidirectional"))
      (node (ref "IC3") (pin "3") (pinfunction "SHDN__3") (pintype "bidirectional"))
      (node (ref "IC7") (pin "1") (pinfunction "VIN_1") (pintype "bidirectional"))
      (node (ref "IC7") (pin "2") (pinfunction "VIN_2") (pintype "bidirectional"))
      (node (ref "IC7") (pin "3") (pinfunction "SHDN__3") (pintype "bidirectional"))
      (node (ref "M7") (pin "1") (pinfunction "VIN_1") (pintype "bidirectional"))
      (node (ref "M7") (pin "EP") (pinfunction "EP_EP") (pintype "bidirectional"))
      (node (ref "M8") (pin "1") (pinfunction "VIN_1") (pintype "bidirectional"))
      (node (ref "M8") (pin "EP") (pinfunction "EP_EP") (pintype "bidirectional"))
      (node (ref "M9") (pin "1") (pinfunction "VIN_1") (pintype "bidirectional"))
      (node (ref "M9") (pin "EP") (pinfunction "EP_EP") (pintype "bidirectional"))
      (node (ref "USB/SWD") (pin "5") (pinfunction "1_5") (pintype "input"))
      (node (ref "X1") (pin "4") (pinfunction "S_4") (pintype "passive"))
    )
    (net (code "60") (name "WS") (class "Default")
      (node (ref "IC1") (pin "W24") (pinfunction "P1.02_W24") (pintype "bidirectional"))
      (node (ref "IC5") (pin "5") (pinfunction "WS_5") (pintype "bidirectional"))
      (node (ref "IC6") (pin "5") (pinfunction "WS_5") (pintype "bidirectional"))
    )
    (net (code "61") (name "unconnected-(IC1-DCC-PadB3)") (class "Default")
      (node (ref "IC1") (pin "B3") (pinfunction "DCC_B3") (pintype "bidirectional"))
    )
    (net (code "62") (name "unconnected-(IC1-DCCH-PadAB2)") (class "Default")
      (node (ref "IC1") (pin "AB2") (pinfunction "DCCH_AB2") (pintype "bidirectional"))
    )
    (net (code "63") (name "unconnected-(IC1-P0.03-PadB13)") (class "Default")
      (node (ref "IC1") (pin "B13") (pinfunction "P0.03_B13") (pintype "bidirectional"))
    )
    (net (code "64") (name "unconnected-(IC1-P0.05{slash}AN13-PadK2)") (class "Default")
      (node (ref "IC1") (pin "K2") (pinfunction "P0.05/AN13_K2") (pintype "bidirectional"))
    )
    (net (code "65") (name "unconnected-(IC1-P0.07-PadM2)") (class "Default")
      (node (ref "IC1") (pin "M2") (pinfunction "P0.07_M2") (pintype "bidirectional"))
    )
    (net (code "66") (name "unconnected-(IC1-P0.09-PadL24)") (class "Default")
      (node (ref "IC1") (pin "L24") (pinfunction "P0.09_L24") (pintype "bidirectional"))
    )
    (net (code "67") (name "unconnected-(IC1-P0.10-PadJ24)") (class "Default")
      (node (ref "IC1") (pin "J24") (pinfunction "P0.10_J24") (pintype "bidirectional"))
    )
    (net (code "68") (name "unconnected-(IC1-P0.11-PadT2)") (class "Default")
      (node (ref "IC1") (pin "T2") (pinfunction "P0.11_T2") (pintype "bidirectional"))
    )
    (net (code "69") (name "unconnected-(IC1-P0.14-PadAC9)") (class "Default")
      (node (ref "IC1") (pin "AC9") (pinfunction "P0.14_AC9") (pintype "bidirectional"))
    )
    (net (code "70") (name "unconnected-(IC1-P0.16-PadAC11)") (class "Default")
      (node (ref "IC1") (pin "AC11") (pinfunction "P0.16_AC11") (pintype "bidirectional"))
    )
    (net (code "71") (name "unconnected-(IC1-P0.18{slash}RST-PadAC13)") (class "Default")
      (node (ref "IC1") (pin "AC13") (pinfunction "P0.18/RST_AC13") (pintype "bidirectional"))
    )
    (net (code "72") (name "unconnected-(IC1-P0.19-PadAC15)") (class "Default")
      (node (ref "IC1") (pin "AC15") (pinfunction "P0.19_AC15") (pintype "bidirectional"))
    )
    (net (code "73") (name "unconnected-(IC1-P0.21-PadAC17)") (class "Default")
      (node (ref "IC1") (pin "AC17") (pinfunction "P0.21_AC17") (pintype "bidirectional"))
    )
    (net (code "74") (name "unconnected-(IC1-P0.23-PadAC19)") (class "Default")
      (node (ref "IC1") (pin "AC19") (pinfunction "P0.23_AC19") (pintype "bidirectional"))
    )
    (net (code "75") (name "unconnected-(IC1-P0.25-PadAC21)") (class "Default")
      (node (ref "IC1") (pin "AC21") (pinfunction "P0.25_AC21") (pintype "bidirectional"))
    )
    (net (code "76") (name "unconnected-(IC1-P0.27-PadH2)") (class "Default")
      (node (ref "IC1") (pin "H2") (pinfunction "P0.27_H2") (pintype "bidirectional"))
    )
    (net (code "77") (name "unconnected-(IC1-P0.28-PadB11)") (class "Default")
      (node (ref "IC1") (pin "B11") (pinfunction "P0.28_B11") (pintype "bidirectional"))
    )
    (net (code "78") (name "unconnected-(IC1-P0.30-PadB9)") (class "Default")
      (node (ref "IC1") (pin "B9") (pinfunction "P0.30_B9") (pintype "bidirectional"))
    )
    (net (code "79") (name "unconnected-(IC1-P1.01-PadY23)") (class "Default")
      (node (ref "IC1") (pin "Y23") (pinfunction "P1.01_Y23") (pintype "bidirectional"))
    )
    (net (code "80") (name "unconnected-(IC1-P1.03-PadV23)") (class "Default")
      (node (ref "IC1") (pin "V23") (pinfunction "P1.03_V23") (pintype "bidirectional"))
    )
    (net (code "81") (name "unconnected-(IC1-P1.05-PadT23)") (class "Default")
      (node (ref "IC1") (pin "T23") (pinfunction "P1.05_T23") (pintype "bidirectional"))
    )
    (net (code "82") (name "unconnected-(IC1-P1.07-PadP23)") (class "Default")
      (node (ref "IC1") (pin "P23") (pinfunction "P1.07_P23") (pintype "bidirectional"))
    )
    (net (code "83") (name "unconnected-(IC1-P1.08-PadP2)") (class "Default")
      (node (ref "IC1") (pin "P2") (pinfunction "P1.08_P2") (pintype "bidirectional"))
    )
    (net (code "84") (name "unconnected-(IC1-P1.11-PadB19)") (class "Default")
      (node (ref "IC1") (pin "B19") (pinfunction "P1.11_B19") (pintype "bidirectional"))
    )
    (net (code "85") (name "unconnected-(IC1-P1.12-PadB17)") (class "Default")
      (node (ref "IC1") (pin "B17") (pinfunction "P1.12_B17") (pintype "bidirectional"))
    )
    (net (code "86") (name "unconnected-(IC1-P1.14-PadB15)") (class "Default")
      (node (ref "IC1") (pin "B15") (pinfunction "P1.14_B15") (pintype "bidirectional"))
    )
    (net (code "87") (name "unconnected-(IC2-NC-Pad2)") (class "Default")
      (node (ref "IC2") (pin "2") (pinfunction "NC_2") (pintype "bidirectional"))
    )
    (net (code "88") (name "unconnected-(IC2-NC-Pad3)") (class "Default")
      (node (ref "IC2") (pin "3") (pinfunction "NC_3") (pintype "bidirectional"))
    )
    (net (code "89") (name "unconnected-(IC2-NC-Pad4)") (class "Default")
      (node (ref "IC2") (pin "4") (pinfunction "NC_4") (pintype "bidirectional"))
    )
    (net (code "90") (name "unconnected-(IC2-NC-Pad5)") (class "Default")
      (node (ref "IC2") (pin "5") (pinfunction "NC_5") (pintype "bidirectional"))
    )
    (net (code "91") (name "unconnected-(IC2-NC-Pad6)") (class "Default")
      (node (ref "IC2") (pin "6") (pinfunction "NC_6") (pintype "bidirectional"))
    )
    (net (code "92") (name "unconnected-(IC2-NC-Pad14)") (class "Default")
      (node (ref "IC2") (pin "14") (pinfunction "NC_14") (pintype "bidirectional"))
    )
    (net (code "93") (name "unconnected-(IC2-NC-Pad15)") (class "Default")
      (node (ref "IC2") (pin "15") (pinfunction "NC_15") (pintype "bidirectional"))
    )
    (net (code "94") (name "unconnected-(IC2-NC-Pad16)") (class "Default")
      (node (ref "IC2") (pin "16") (pinfunction "NC_16") (pintype "bidirectional"))
    )
    (net (code "95") (name "unconnected-(IC2-NC-Pad17)") (class "Default")
      (node (ref "IC2") (pin "17") (pinfunction "NC_17") (pintype "bidirectional"))
    )
    (net (code "96") (name "unconnected-(IC2-RESV-Pad1)") (class "Default")
      (node (ref "IC2") (pin "1") (pinfunction "RESV_1") (pintype "bidirectional"))
    )
    (net (code "97") (name "unconnected-(IC2-RESV-Pad19)") (class "Default")
      (node (ref "IC2") (pin "19") (pinfunction "RESV_19") (pintype "bidirectional"))
    )
    (net (code "98") (name "unconnected-(IC2-RESV-Pad20)") (class "Default")
      (node (ref "IC2") (pin "20") (pinfunction "RESV_20") (pintype "bidirectional"))
    )
    (net (code "99") (name "unconnected-(USB/SWDA-S1-PadM1)") (class "Default")
      (node (ref "USB/SWD") (pin "M1") (pinfunction "S1_M1") (pintype "passive"))
    )
    (net (code "100") (name "unconnected-(USB/SWDA-S2-PadM2)") (class "Default")
      (node (ref "USB/SWD") (pin "M2") (pinfunction "S2_M2") (pintype "passive"))
    )
    (net (code "101") (name "unconnected-(USB/SWDA-S3-PadM3)") (class "Default")
      (node (ref "USB/SWD") (pin "M3") (pinfunction "S3_M3") (pintype "passive"))
    )
    (net (code "102") (name "unconnected-(USB/SWDA-S4-PadM4)") (class "Default")
      (node (ref "USB/SWD") (pin "M4") (pinfunction "S4_M4") (pintype "passive"))
    )
    (net (code "103") (name "unconnected-(USB/SWDB-4-Pad2)") (class "Default")
      (node (ref "USB/SWD") (pin "2") (pinfunction "4_2") (pintype "input"))
    )
  )
)
